# can_bridge.net
KiCad netlist of a schematic drawn in Altium Designer
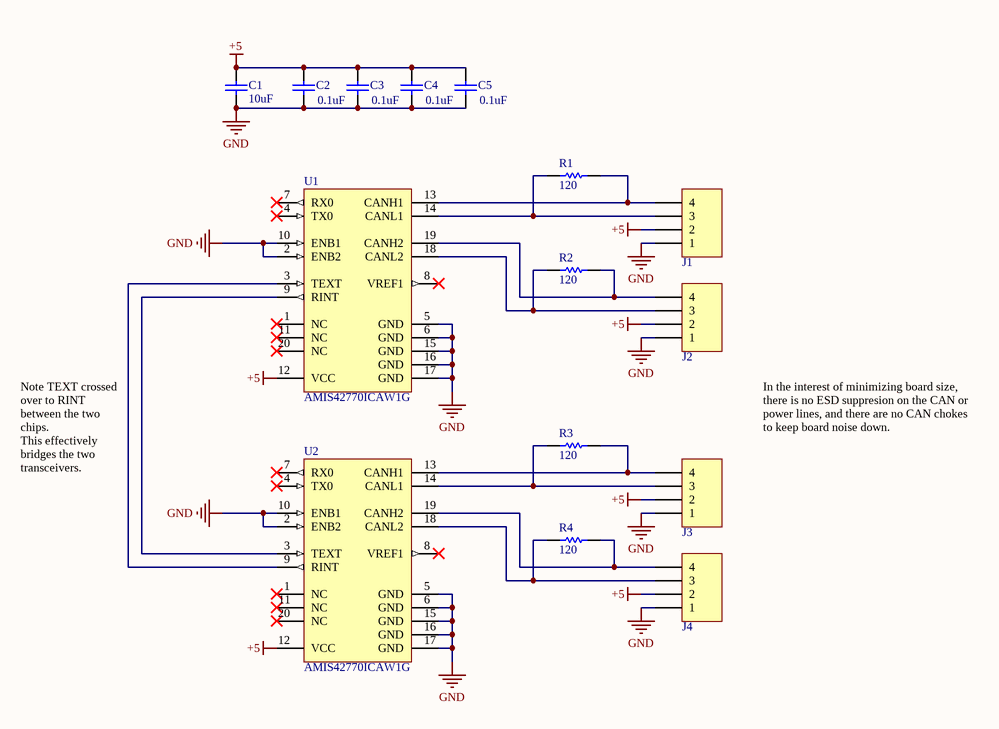
[diagram p0: can_bridge.SchDoc]

(export (version "E")
  (design (tool "Eeschema 10.0.6"))
  (components
    (comp (ref "C1")
      (value "Cap")
      (footprint "CAP_0805")
      (description "CAP CER 10UF 10V X5R 0805")
      (fields (field (name "CAPACITANCE") "10uF"))
      (libsource (lib "can_bridge") (part "LMK212BJ106KG-T"))
    )
    (comp (ref "C2")
      (value "Cap")
      (footprint "CAP_0603")
      (description "CAP CER 0.1UF 16V X7R 0603")
      (fields (field (name "CAPACITANCE") "0.1uF"))
      (libsource (lib "can_bridge") (part "EMK107B7104KA-T"))
    )
    (comp (ref "C3")
      (value "Cap")
      (footprint "CAP_0603")
      (description "CAP CER 0.1UF 16V X7R 0603")
      (fields (field (name "CAPACITANCE") "0.1uF"))
      (libsource (lib "can_bridge") (part "EMK107B7104KA-T"))
    )
    (comp (ref "C4")
      (value "Cap")
      (footprint "CAP_0603")
      (description "CAP CER 0.1UF 16V X7R 0603")
      (fields (field (name "CAPACITANCE") "0.1uF"))
      (libsource (lib "can_bridge") (part "EMK107B7104KA-T"))
    )
    (comp (ref "C5")
      (value "Cap")
      (footprint "CAP_0603")
      (description "CAP CER 0.1UF 16V X7R 0603")
      (fields (field (name "CAPACITANCE") "0.1uF"))
      (libsource (lib "can_bridge") (part "EMK107B7104KA-T"))
    )
    (comp (ref "J1")
      (value "0430450401")
      (footprint "Molex_0430450401")
      (description "HEADER R/A 4POS DUAL GOLD T/H")
      (libsource (lib "can_bridge") (part "0430450401"))
    )
    (comp (ref "J2")
      (value "0430450401")
      (footprint "Molex_0430450401")
      (description "HEADER R/A 4POS DUAL GOLD T/H")
      (libsource (lib "can_bridge") (part "0430450401"))
    )
    (comp (ref "J3")
      (value "0430450401")
      (footprint "Molex_0430450401")
      (description "HEADER R/A 4POS DUAL GOLD T/H")
      (libsource (lib "can_bridge") (part "0430450401"))
    )
    (comp (ref "J4")
      (value "0430450401")
      (footprint "Molex_0430450401")
      (description "HEADER R/A 4POS DUAL GOLD T/H")
      (libsource (lib "can_bridge") (part "0430450401"))
    )
    (comp (ref "R1")
      (value "Res1")
      (footprint "RES_0603")
      (fields (field (name "RESISTANCE") "120"))
      (libsource (lib "can_bridge") (part "ERJ-3EKF1200V"))
    )
    (comp (ref "R2")
      (value "Res1")
      (footprint "RES_0603")
      (fields (field (name "RESISTANCE") "120"))
      (libsource (lib "can_bridge") (part "ERJ-3EKF1200V"))
    )
    (comp (ref "R3")
      (value "Res1")
      (footprint "RES_0603")
      (fields (field (name "RESISTANCE") "120"))
      (libsource (lib "can_bridge") (part "ERJ-3EKF1200V"))
    )
    (comp (ref "R4")
      (value "Res1")
      (footprint "RES_0603")
      (fields (field (name "RESISTANCE") "120"))
      (libsource (lib "can_bridge") (part "ERJ-3EKF1200V"))
    )
    (comp (ref "U1")
      (value "AMIS42770ICAW1G")
      (footprint "ONSC-SOIC-20-751AQ-01_N")
      (description "Dual High Speed CAN Transceivers, 4.75 to 5.25 V, -40 to 125 degC, 20-Pin SOIC, Pb-Free, Tube")
      (fields (field (name "MANUFACTURER") "On Semiconductor"))
      (libsource (lib "Altium Content Vault") (part "CMP-1313-00055-1"))
    )
    (comp (ref "U2")
      (value "AMIS42770ICAW1G")
      (footprint "ONSC-SOIC-20-751AQ-01_N")
      (description "Dual High Speed CAN Transceivers, 4.75 to 5.25 V, -40 to 125 degC, 20-Pin SOIC, Pb-Free, Tube")
      (fields (field (name "MANUFACTURER") "On Semiconductor"))
      (libsource (lib "Altium Content Vault") (part "CMP-1313-00055-1"))
    )
  )
  (nets
    (net (code "1") (name "+5") (class "Default")
      (node (ref "C1") (pin "2") (pinfunction "2_2") (pintype "passive"))
      (node (ref "C2") (pin "2") (pinfunction "2_2") (pintype "passive"))
      (node (ref "C3") (pin "2") (pinfunction "2_2") (pintype "passive"))
      (node (ref "C4") (pin "2") (pinfunction "2_2") (pintype "passive"))
      (node (ref "C5") (pin "2") (pinfunction "2_2") (pintype "passive"))
      (node (ref "J1") (pin "2") (pinfunction "2_2") (pintype "passive"))
      (node (ref "J2") (pin "2") (pinfunction "2_2") (pintype "passive"))
      (node (ref "J3") (pin "2") (pinfunction "2_2") (pintype "passive"))
      (node (ref "J4") (pin "2") (pinfunction "2_2") (pintype "passive"))
      (node (ref "U1") (pin "12") (pinfunction "VCC_12") (pintype "power_in"))
      (node (ref "U2") (pin "12") (pinfunction "VCC_12") (pintype "power_in"))
    )
    (net (code "2") (name "GND") (class "Default")
      (node (ref "C1") (pin "1") (pinfunction "1_1") (pintype "passive"))
      (node (ref "C2") (pin "1") (pinfunction "1_1") (pintype "passive"))
      (node (ref "C3") (pin "1") (pinfunction "1_1") (pintype "passive"))
      (node (ref "C4") (pin "1") (pinfunction "1_1") (pintype "passive"))
      (node (ref "C5") (pin "1") (pinfunction "1_1") (pintype "passive"))
      (node (ref "J1") (pin "1") (pinfunction "1_1") (pintype "passive"))
      (node (ref "J2") (pin "1") (pinfunction "1_1") (pintype "passive"))
      (node (ref "J3") (pin "1") (pinfunction "1_1") (pintype "passive"))
      (node (ref "J4") (pin "1") (pinfunction "1_1") (pintype "passive"))
      (node (ref "U1") (pin "10") (pinfunction "ENB1_10") (pintype "input"))
      (node (ref "U1") (pin "15") (pinfunction "GND_15") (pintype "power_in"))
      (node (ref "U1") (pin "16") (pinfunction "GND_16") (pintype "power_in"))
      (node (ref "U1") (pin "17") (pinfunction "GND_17") (pintype "power_in"))
      (node (ref "U1") (pin "2") (pinfunction "ENB2_2") (pintype "input"))
      (node (ref "U1") (pin "5") (pinfunction "GND_5") (pintype "power_in"))
      (node (ref "U1") (pin "6") (pinfunction "GND_6") (pintype "power_in"))
      (node (ref "U2") (pin "10") (pinfunction "ENB1_10") (pintype "input"))
      (node (ref "U2") (pin "15") (pinfunction "GND_15") (pintype "power_in"))
      (node (ref "U2") (pin "16") (pinfunction "GND_16") (pintype "power_in"))
      (node (ref "U2") (pin "17") (pinfunction "GND_17") (pintype "power_in"))
      (node (ref "U2") (pin "2") (pinfunction "ENB2_2") (pintype "input"))
      (node (ref "U2") (pin "5") (pinfunction "GND_5") (pintype "power_in"))
      (node (ref "U2") (pin "6") (pinfunction "GND_6") (pintype "power_in"))
    )
    (net (code "3") (name "Net-(U1-CANH1)") (class "Default")
      (node (ref "J1") (pin "4") (pinfunction "4_4") (pintype "passive"))
      (node (ref "R1") (pin "2") (pinfunction "2_2") (pintype "passive"))
      (node (ref "U1") (pin "13") (pinfunction "CANH1_13") (pintype "passive"))
    )
    (net (code "4") (name "Net-(U1-CANH2)") (class "Default")
      (node (ref "J2") (pin "4") (pinfunction "4_4") (pintype "passive"))
      (node (ref "R2") (pin "2") (pinfunction "2_2") (pintype "passive"))
      (node (ref "U1") (pin "19") (pinfunction "CANH2_19") (pintype "passive"))
    )
    (net (code "5") (name "Net-(U1-CANL1)") (class "Default")
      (node (ref "J1") (pin "3") (pinfunction "3_3") (pintype "passive"))
      (node (ref "R1") (pin "1") (pinfunction "1_1") (pintype "passive"))
      (node (ref "U1") (pin "14") (pinfunction "CANL1_14") (pintype "passive"))
    )
    (net (code "6") (name "Net-(U1-CANL2)") (class "Default")
      (node (ref "J2") (pin "3") (pinfunction "3_3") (pintype "passive"))
      (node (ref "R2") (pin "1") (pinfunction "1_1") (pintype "passive"))
      (node (ref "U1") (pin "18") (pinfunction "CANL2_18") (pintype "passive"))
    )
    (net (code "7") (name "Net-(U1-RINT)") (class "Default")
      (node (ref "U1") (pin "9") (pinfunction "RINT_9") (pintype "output"))
      (node (ref "U2") (pin "3") (pinfunction "TEXT_3") (pintype "input"))
    )
    (net (code "8") (name "Net-(U1-TEXT)") (class "Default")
      (node (ref "U1") (pin "3") (pinfunction "TEXT_3") (pintype "input"))
      (node (ref "U2") (pin "9") (pinfunction "RINT_9") (pintype "output"))
    )
    (net (code "9") (name "Net-(U2-CANH1)") (class "Default")
      (node (ref "J3") (pin "4") (pinfunction "4_4") (pintype "passive"))
      (node (ref "R3") (pin "2") (pinfunction "2_2") (pintype "passive"))
      (node (ref "U2") (pin "13") (pinfunction "CANH1_13") (pintype "passive"))
    )
    (net (code "10") (name "Net-(U2-CANH2)") (class "Default")
      (node (ref "J4") (pin "4") (pinfunction "4_4") (pintype "passive"))
      (node (ref "R4") (pin "2") (pinfunction "2_2") (pintype "passive"))
      (node (ref "U2") (pin "19") (pinfunction "CANH2_19") (pintype "passive"))
    )
    (net (code "11") (name "Net-(U2-CANL1)") (class "Default")
      (node (ref "J3") (pin "3") (pinfunction "3_3") (pintype "passive"))
      (node (ref "R3") (pin "1") (pinfunction "1_1") (pintype "passive"))
      (node (ref "U2") (pin "14") (pinfunction "CANL1_14") (pintype "passive"))
    )
    (net (code "12") (name "Net-(U2-CANL2)") (class "Default")
      (node (ref "J4") (pin "3") (pinfunction "3_3") (pintype "passive"))
      (node (ref "R4") (pin "1") (pinfunction "1_1") (pintype "passive"))
      (node (ref "U2") (pin "18") (pinfunction "CANL2_18") (pintype "passive"))
    )
    (net (code "13") (name "unconnected-(U1-NC-Pad1)") (class "Default")
      (node (ref "U1") (pin "1") (pinfunction "NC_1") (pintype "passive+no_connect"))
    )
    (net (code "14") (name "unconnected-(U1-NC-Pad11)") (class "Default")
      (node (ref "U1") (pin "11") (pinfunction "NC_11") (pintype "passive+no_connect"))
    )
    (net (code "15") (name "unconnected-(U1-NC-Pad20)") (class "Default")
      (node (ref "U1") (pin "20") (pinfunction "NC_20") (pintype "passive+no_connect"))
    )
    (net (code "16") (name "unconnected-(U1-RX0-Pad7)") (class "Default")
      (node (ref "U1") (pin "7") (pinfunction "RX0_7") (pintype "output+no_connect"))
    )
    (net (code "17") (name "unconnected-(U1-TX0-Pad4)") (class "Default")
      (node (ref "U1") (pin "4") (pinfunction "TX0_4") (pintype "input+no_connect"))
    )
    (net (code "18") (name "unconnected-(U1-VREF1-Pad8)") (class "Default")
      (node (ref "U1") (pin "8") (pinfunction "VREF1_8") (pintype "output+no_connect"))
    )
    (net (code "19") (name "unconnected-(U2-NC-Pad1)") (class "Default")
      (node (ref "U2") (pin "1") (pinfunction "NC_1") (pintype "passive+no_connect"))
    )
    (net (code "20") (name "unconnected-(U2-NC-Pad11)") (class "Default")
      (node (ref "U2") (pin "11") (pinfunction "NC_11") (pintype "passive+no_connect"))
    )
    (net (code "21") (name "unconnected-(U2-NC-Pad20)") (class "Default")
      (node (ref "U2") (pin "20") (pinfunction "NC_20") (pintype "passive+no_connect"))
    )
    (net (code "22") (name "unconnected-(U2-RX0-Pad7)") (class "Default")
      (node (ref "U2") (pin "7") (pinfunction "RX0_7") (pintype "output+no_connect"))
    )
    (net (code "23") (name "unconnected-(U2-TX0-Pad4)") (class "Default")
      (node (ref "U2") (pin "4") (pinfunction "TX0_4") (pintype "input+no_connect"))
    )
    (net (code "24") (name "unconnected-(U2-VREF1-Pad8)") (class "Default")
      (node (ref "U2") (pin "8") (pinfunction "VREF1_8") (pintype "output+no_connect"))
    )
  )
)
